# board.net
KiCad netlist of a schematic drawn in EAGLE
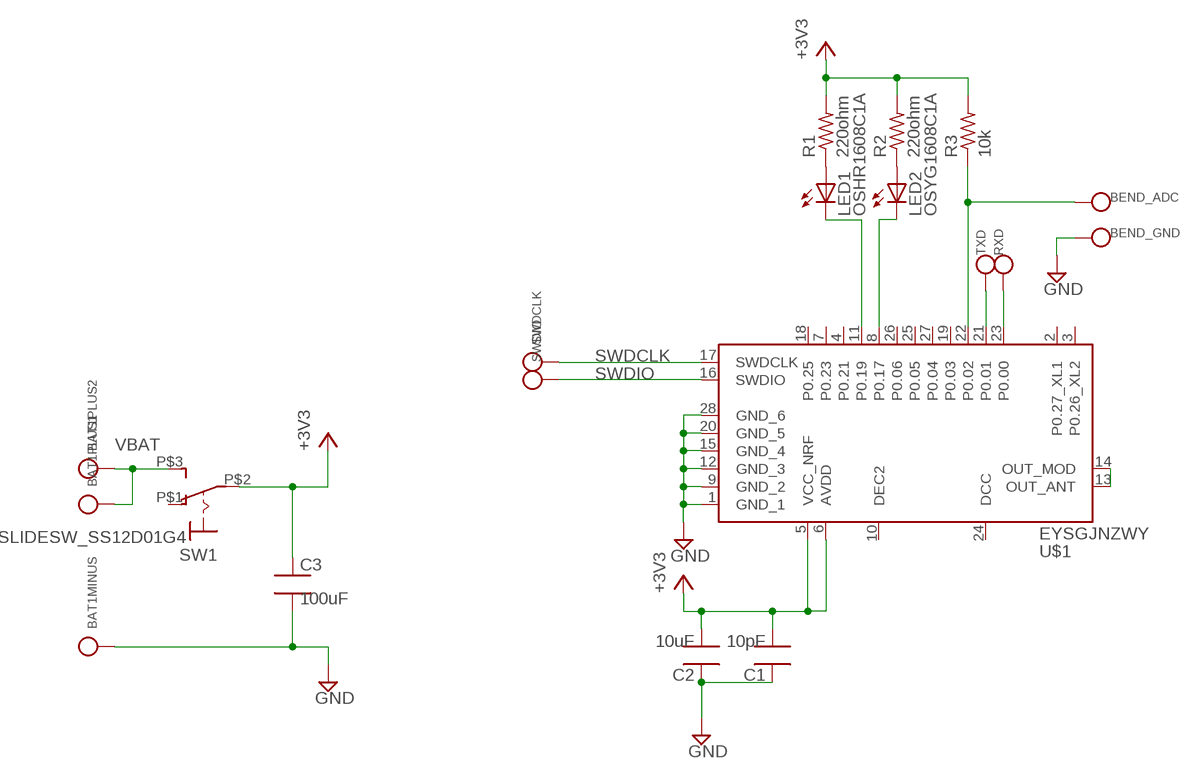
[diagram p0: schematic, sheet 1]

(export (version "E")
  (design (tool "Eeschema 10.0.6"))
  (components
    (comp (ref "BAT1")
      (value "BATTERY")
      (footprint "eagle-import:CR1025")
      (libsource (lib "eagle-import") (part "BATTERY"))
    )
    (comp (ref "BEND_ADC")
      (value "CHECK_PIN-SMD_100*60")
      (footprint "eagle-import:SMD_100_60")
      (libsource (lib "eagle-import") (part "CHECK_PIN-SMD_10060"))
    )
    (comp (ref "BEND_GND")
      (value "CHECK_PIN-SMD_100*60")
      (footprint "eagle-import:SMD_100_60")
      (libsource (lib "eagle-import") (part "CHECK_PIN-SMD_10060"))
    )
    (comp (ref "C1")
      (value "10pF")
      (footprint "eagle-import:1005")
      (libsource (lib "eagle-import") (part "C-1005"))
    )
    (comp (ref "C2")
      (value "10uF")
      (footprint "eagle-import:1005")
      (libsource (lib "eagle-import") (part "C-1005"))
    )
    (comp (ref "C3")
      (value "100uF")
      (footprint "eagle-import:3216")
      (libsource (lib "eagle-import") (part "C-3216"))
    )
    (comp (ref "LED1")
      (value "OSHR1608C1A")
      (footprint "eagle-import:1608-LED")
      (libsource (lib "eagle-import") (part "OS1608C1AHR"))
    )
    (comp (ref "LED2")
      (value "OSYG1608C1A")
      (footprint "eagle-import:1608-LED")
      (libsource (lib "eagle-import") (part "OS1608C1AYG"))
    )
    (comp (ref "R1")
      (value "220ohm")
      (footprint "eagle-import:1608")
      (libsource (lib "eagle-import") (part "R-1608"))
    )
    (comp (ref "R2")
      (value "220ohm")
      (footprint "eagle-import:1608")
      (libsource (lib "eagle-import") (part "R-1608"))
    )
    (comp (ref "R3")
      (value "10k")
      (footprint "eagle-import:1608")
      (libsource (lib "eagle-import") (part "R-1608"))
    )
    (comp (ref "RXD")
      (value "CHECK_PIN-SMD_100*60")
      (footprint "eagle-import:SMD_100_60")
      (libsource (lib "eagle-import") (part "CHECK_PIN-SMD_10060"))
    )
    (comp (ref "SW1")
      (value "SLIDESW_SS12D01G4")
      (footprint "eagle-import:SS12D01G4")
      (libsource (lib "eagle-import") (part "SLIDESW_SS12D01G4"))
    )
    (comp (ref "SWDCLK")
      (value "CHECK_PIN-SMD_100*60")
      (footprint "eagle-import:SMD_100_60")
      (libsource (lib "eagle-import") (part "CHECK_PIN-SMD_10060"))
    )
    (comp (ref "SWDIO")
      (value "CHECK_PIN-SMD_100*60")
      (footprint "eagle-import:SMD_100_60")
      (libsource (lib "eagle-import") (part "CHECK_PIN-SMD_10060"))
    )
    (comp (ref "TXD")
      (value "CHECK_PIN-SMD_100*60")
      (footprint "eagle-import:SMD_100_60")
      (libsource (lib "eagle-import") (part "CHECK_PIN-SMD_10060"))
    )
    (comp (ref "U$1")
      (value "EYSGJNZWY")
      (footprint "eagle-import:TAIYOYUDEN_BT_XXXXJN")
      (libsource (lib "eagle-import") (part "EYSGJNZWY"))
    )
  )
  (nets
    (net (code "1") (name "+3V3") (class "Default")
      (node (ref "C1") (pin "2") (pinfunction "2_2") (pintype "passive"))
      (node (ref "C2") (pin "2") (pinfunction "2_2") (pintype "passive"))
      (node (ref "C3") (pin "1") (pinfunction "1_1") (pintype "passive"))
      (node (ref "R1") (pin "2") (pinfunction "2_2") (pintype "passive"))
      (node (ref "R2") (pin "2") (pinfunction "2_2") (pintype "passive"))
      (node (ref "R3") (pin "2") (pinfunction "2_2") (pintype "passive"))
      (node (ref "SW1") (pin "P$2") (pinfunction "P_P$2") (pintype "passive"))
      (node (ref "U$1") (pin "5") (pinfunction "VCC_NRF_5") (pintype "bidirectional"))
      (node (ref "U$1") (pin "6") (pinfunction "AVDD_6") (pintype "bidirectional"))
    )
    (net (code "2") (name "/SWDCLK") (class "Default")
      (node (ref "SWDCLK") (pin "SIGNAL") (pinfunction "SIGNAL_SIGNAL") (pintype "bidirectional"))
      (node (ref "U$1") (pin "17") (pinfunction "SWDCLK_17") (pintype "bidirectional"))
    )
    (net (code "3") (name "/SWDIO") (class "Default")
      (node (ref "SWDIO") (pin "SIGNAL") (pinfunction "SIGNAL_SIGNAL") (pintype "bidirectional"))
      (node (ref "U$1") (pin "16") (pinfunction "SWDIO_16") (pintype "bidirectional"))
    )
    (net (code "4") (name "/VBAT") (class "Default")
      (node (ref "BAT1") (pin "+_1") (pinfunction "SIGNAL_+_1") (pintype "bidirectional"))
      (node (ref "BAT1") (pin "+_2") (pinfunction "SIGNAL_+_2") (pintype "bidirectional"))
      (node (ref "SW1") (pin "P$3") (pinfunction "S_P$3") (pintype "passive"))
    )
    (net (code "5") (name "GND") (class "Default")
      (node (ref "BAT1") (pin "-") (pinfunction "SIGNAL_-") (pintype "bidirectional"))
      (node (ref "BEND_GND") (pin "SIGNAL") (pinfunction "SIGNAL_SIGNAL") (pintype "bidirectional"))
      (node (ref "C1") (pin "1") (pinfunction "1_1") (pintype "passive"))
      (node (ref "C2") (pin "1") (pinfunction "1_1") (pintype "passive"))
      (node (ref "C3") (pin "2") (pinfunction "2_2") (pintype "passive"))
      (node (ref "U$1") (pin "1") (pinfunction "GND_1_1") (pintype "bidirectional"))
      (node (ref "U$1") (pin "12") (pinfunction "GND_3_12") (pintype "bidirectional"))
      (node (ref "U$1") (pin "15") (pinfunction "GND_4_15") (pintype "bidirectional"))
      (node (ref "U$1") (pin "20") (pinfunction "GND_5_20") (pintype "bidirectional"))
      (node (ref "U$1") (pin "28") (pinfunction "GND_6_28") (pintype "bidirectional"))
      (node (ref "U$1") (pin "9") (pinfunction "GND_2_9") (pintype "bidirectional"))
    )
    (net (code "6") (name "Net-(LED1-A)") (class "Default")
      (node (ref "LED1") (pin "1") (pinfunction "A_1") (pintype "passive"))
      (node (ref "R1") (pin "1") (pinfunction "1_1") (pintype "passive"))
    )
    (net (code "7") (name "Net-(LED1-K)") (class "Default")
      (node (ref "LED1") (pin "2") (pinfunction "K_2") (pintype "passive"))
      (node (ref "U$1") (pin "11") (pinfunction "P0.19_11") (pintype "bidirectional"))
    )
    (net (code "8") (name "Net-(LED2-A)") (class "Default")
      (node (ref "LED2") (pin "1") (pinfunction "A_1") (pintype "passive"))
      (node (ref "R2") (pin "1") (pinfunction "1_1") (pintype "passive"))
    )
    (net (code "9") (name "Net-(LED2-K)") (class "Default")
      (node (ref "LED2") (pin "2") (pinfunction "K_2") (pintype "passive"))
      (node (ref "U$1") (pin "8") (pinfunction "P0.17_8") (pintype "bidirectional"))
    )
    (net (code "10") (name "Net-(U$1-OUT_ANT)") (class "Default")
      (node (ref "U$1") (pin "13") (pinfunction "OUT_ANT_13") (pintype "bidirectional"))
      (node (ref "U$1") (pin "14") (pinfunction "OUT_MOD_14") (pintype "bidirectional"))
    )
    (net (code "11") (name "Net-(U$1-P0.00)") (class "Default")
      (node (ref "RXD") (pin "SIGNAL") (pinfunction "SIGNAL_SIGNAL") (pintype "bidirectional"))
      (node (ref "U$1") (pin "23") (pinfunction "P0.00_23") (pintype "bidirectional"))
    )
    (net (code "12") (name "Net-(U$1-P0.01)") (class "Default")
      (node (ref "TXD") (pin "SIGNAL") (pinfunction "SIGNAL_SIGNAL") (pintype "bidirectional"))
      (node (ref "U$1") (pin "21") (pinfunction "P0.01_21") (pintype "bidirectional"))
    )
    (net (code "13") (name "Net-(U$1-P0.02)") (class "Default")
      (node (ref "BEND_ADC") (pin "SIGNAL") (pinfunction "SIGNAL_SIGNAL") (pintype "bidirectional"))
      (node (ref "R3") (pin "1") (pinfunction "1_1") (pintype "passive"))
      (node (ref "U$1") (pin "22") (pinfunction "P0.02_22") (pintype "bidirectional"))
    )
    (net (code "14") (name "unconnected-(SW1-O-PadP$1)") (class "Default")
      (node (ref "SW1") (pin "P$1") (pinfunction "O_P$1") (pintype "passive"))
    )
    (net (code "15") (name "unconnected-(U$1-DCC-Pad24)") (class "Default")
      (node (ref "U$1") (pin "24") (pinfunction "DCC_24") (pintype "bidirectional"))
    )
    (net (code "16") (name "unconnected-(U$1-DEC2-Pad10)") (class "Default")
      (node (ref "U$1") (pin "10") (pinfunction "DEC2_10") (pintype "bidirectional"))
    )
    (net (code "17") (name "unconnected-(U$1-P0.03-Pad19)") (class "Default")
      (node (ref "U$1") (pin "19") (pinfunction "P0.03_19") (pintype "bidirectional"))
    )
    (net (code "18") (name "unconnected-(U$1-P0.04-Pad27)") (class "Default")
      (node (ref "U$1") (pin "27") (pinfunction "P0.04_27") (pintype "bidirectional"))
    )
    (net (code "19") (name "unconnected-(U$1-P0.05-Pad25)") (class "Default")
      (node (ref "U$1") (pin "25") (pinfunction "P0.05_25") (pintype "bidirectional"))
    )
    (net (code "20") (name "unconnected-(U$1-P0.06-Pad26)") (class "Default")
      (node (ref "U$1") (pin "26") (pinfunction "P0.06_26") (pintype "bidirectional"))
    )
    (net (code "21") (name "unconnected-(U$1-P0.21-Pad4)") (class "Default")
      (node (ref "U$1") (pin "4") (pinfunction "P0.21_4") (pintype "bidirectional"))
    )
    (net (code "22") (name "unconnected-(U$1-P0.23-Pad7)") (class "Default")
      (node (ref "U$1") (pin "7") (pinfunction "P0.23_7") (pintype "bidirectional"))
    )
    (net (code "23") (name "unconnected-(U$1-P0.25-Pad18)") (class "Default")
      (node (ref "U$1") (pin "18") (pinfunction "P0.25_18") (pintype "bidirectional"))
    )
    (net (code "24") (name "unconnected-(U$1-P0.26_XL2-Pad3)") (class "Default")
      (node (ref "U$1") (pin "3") (pinfunction "P0.26_XL2_3") (pintype "bidirectional"))
    )
    (net (code "25") (name "unconnected-(U$1-P0.27_XL1-Pad2)") (class "Default")
      (node (ref "U$1") (pin "2") (pinfunction "P0.27_XL1_2") (pintype "bidirectional"))
    )
  )
)
